# Wireless_Switch.net
KiCad netlist of a schematic drawn in EAGLE
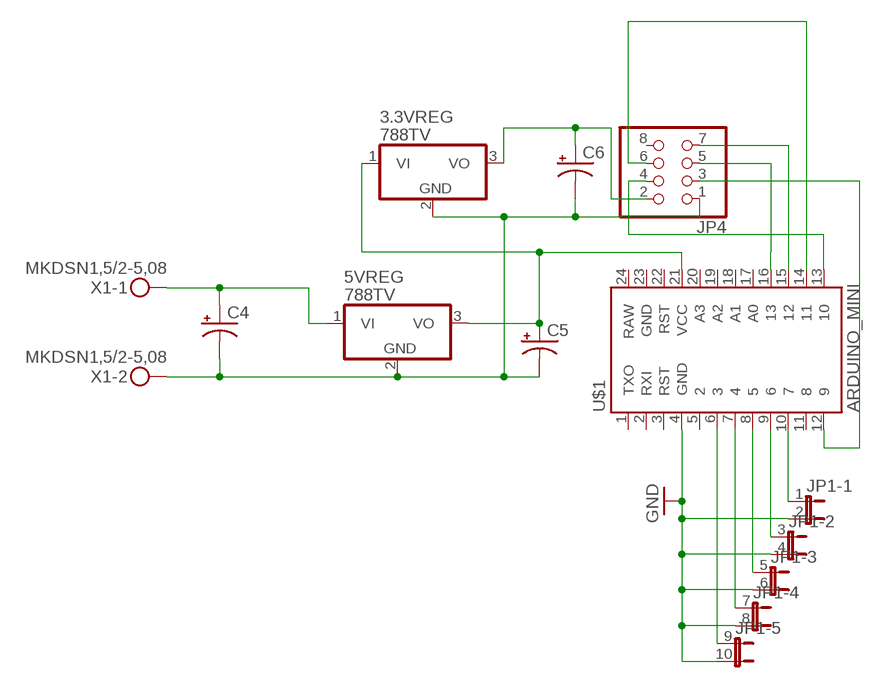
[diagram p0: schematic, sheet 1]

(export (version "E")
  (design (tool "Eeschema 10.0.6"))
  (components
    (comp (ref "3.3VREG")
      (value "788TV")
      (footprint "eagle-import:TO220V")
      (libsource (lib "eagle-import") (part "78TV8"))
    )
    (comp (ref "5VREG")
      (value "788TV")
      (footprint "eagle-import:TO220V")
      (libsource (lib "eagle-import") (part "78TV8"))
    )
    (comp (ref "C4")
      (value "CPOL-USE3.5-8")
      (footprint "eagle-import:E3,5-8")
      (libsource (lib "eagle-import") (part "CPOL-USE3.5-8"))
    )
    (comp (ref "C5")
      (value "CPOL-USE3.5-8")
      (footprint "eagle-import:E3,5-8")
      (libsource (lib "eagle-import") (part "CPOL-USE3.5-8"))
    )
    (comp (ref "C6")
      (value "CPOL-USE2.5-6")
      (footprint "eagle-import:E2,5-6")
      (libsource (lib "eagle-import") (part "CPOL-USE2.5-6"))
    )
    (comp (ref "JP1")
      (value "JP5QE")
      (footprint "eagle-import:JP5Q")
      (libsource (lib "eagle-import") (part "JP5QE"))
    )
    (comp (ref "JP4")
      (value "PINHD-2X4")
      (footprint "eagle-import:2X04")
      (libsource (lib "eagle-import") (part "PINHD-2X4"))
    )
    (comp (ref "U$1")
      (value "ARDUINO_MINI")
      (footprint "eagle-import:ARDUINO_MINI")
      (libsource (lib "eagle-import") (part "ARDUINO_MINI"))
    )
    (comp (ref "X1")
      (value "MKDSN1,5/2-5,08")
      (footprint "eagle-import:MKDSN1,5_2-5,08")
      (libsource (lib "eagle-import") (part "MKDSN1,5/2-5,08"))
    )
  )
  (nets
    (net (code "1") (name "GND") (class "Default")
      (node (ref "JP1") (pin "10") (pinfunction "2_10") (pintype "passive"))
      (node (ref "JP1") (pin "2") (pinfunction "2_2") (pintype "passive"))
      (node (ref "JP1") (pin "4") (pinfunction "2_4") (pintype "passive"))
      (node (ref "JP1") (pin "6") (pinfunction "2_6") (pintype "passive"))
      (node (ref "JP1") (pin "8") (pinfunction "2_8") (pintype "passive"))
      (node (ref "U$1") (pin "4") (pinfunction "GND_4") (pintype "bidirectional"))
    )
    (net (code "2") (name "Net-(3.3VREG-GND)") (class "Default")
      (node (ref "3.3VREG") (pin "2") (pinfunction "GND_2") (pintype "passive"))
      (node (ref "5VREG") (pin "2") (pinfunction "GND_2") (pintype "passive"))
      (node (ref "C4") (pin "-") (pinfunction "-_-") (pintype "passive"))
      (node (ref "C5") (pin "-") (pinfunction "-_-") (pintype "passive"))
      (node (ref "C6") (pin "-") (pinfunction "-_-") (pintype "passive"))
      (node (ref "JP4") (pin "1") (pinfunction "1_1") (pintype "passive"))
      (node (ref "X1") (pin "2") (pinfunction "KL_2") (pintype "passive"))
    )
    (net (code "3") (name "Net-(3.3VREG-VI)") (class "Default")
      (node (ref "3.3VREG") (pin "1") (pinfunction "VI_1") (pintype "input"))
      (node (ref "5VREG") (pin "3") (pinfunction "VO_3") (pintype "passive"))
      (node (ref "C5") (pin "+") (pinfunction "+_+") (pintype "passive"))
      (node (ref "U$1") (pin "21") (pinfunction "VCC_21") (pintype "bidirectional"))
    )
    (net (code "4") (name "Net-(3.3VREG-VO)") (class "Default")
      (node (ref "3.3VREG") (pin "3") (pinfunction "VO_3") (pintype "passive"))
      (node (ref "C6") (pin "+") (pinfunction "+_+") (pintype "passive"))
      (node (ref "JP4") (pin "2") (pinfunction "2_2") (pintype "passive"))
    )
    (net (code "5") (name "Net-(5VREG-VI)") (class "Default")
      (node (ref "5VREG") (pin "1") (pinfunction "VI_1") (pintype "input"))
      (node (ref "C4") (pin "+") (pinfunction "+_+") (pintype "passive"))
      (node (ref "X1") (pin "1") (pinfunction "KL_1") (pintype "passive"))
    )
    (net (code "6") (name "Net-(JP1B-1)") (class "Default")
      (node (ref "JP1") (pin "3") (pinfunction "1_3") (pintype "passive"))
      (node (ref "U$1") (pin "9") (pinfunction "6_9") (pintype "bidirectional"))
    )
    (net (code "7") (name "Net-(JP1C-1)") (class "Default")
      (node (ref "JP1") (pin "5") (pinfunction "1_5") (pintype "passive"))
      (node (ref "U$1") (pin "8") (pinfunction "5_8") (pintype "bidirectional"))
    )
    (net (code "8") (name "Net-(JP1D-1)") (class "Default")
      (node (ref "JP1") (pin "7") (pinfunction "1_7") (pintype "passive"))
      (node (ref "U$1") (pin "7") (pinfunction "4_7") (pintype "bidirectional"))
    )
    (net (code "9") (name "Net-(JP1E-1)") (class "Default")
      (node (ref "JP1") (pin "9") (pinfunction "1_9") (pintype "passive"))
      (node (ref "U$1") (pin "6") (pinfunction "3_6") (pintype "bidirectional"))
    )
    (net (code "10") (name "Net-(U$1-7)") (class "Default")
      (node (ref "JP1") (pin "1") (pinfunction "1_1") (pintype "passive"))
      (node (ref "U$1") (pin "10") (pinfunction "7_10") (pintype "bidirectional"))
    )
    (net (code "11") (name "Net-(U$1-9)") (class "Default")
      (node (ref "JP4") (pin "3") (pinfunction "3_3") (pintype "passive"))
      (node (ref "U$1") (pin "12") (pinfunction "9_12") (pintype "bidirectional"))
    )
    (net (code "12") (name "Net-(U$1-10)") (class "Default")
      (node (ref "JP4") (pin "4") (pinfunction "4_4") (pintype "passive"))
      (node (ref "U$1") (pin "13") (pinfunction "10_13") (pintype "bidirectional"))
    )
    (net (code "13") (name "Net-(U$1-11)") (class "Default")
      (node (ref "JP4") (pin "6") (pinfunction "6_6") (pintype "passive"))
      (node (ref "U$1") (pin "14") (pinfunction "11_14") (pintype "bidirectional"))
    )
    (net (code "14") (name "Net-(U$1-12)") (class "Default")
      (node (ref "JP4") (pin "7") (pinfunction "7_7") (pintype "passive"))
      (node (ref "U$1") (pin "15") (pinfunction "12_15") (pintype "bidirectional"))
    )
    (net (code "15") (name "Net-(U$1-13)") (class "Default")
      (node (ref "JP4") (pin "5") (pinfunction "5_5") (pintype "passive"))
      (node (ref "U$1") (pin "16") (pinfunction "13_16") (pintype "bidirectional"))
    )
    (net (code "16") (name "unconnected-(JP4-Pad8)") (class "Default")
      (node (ref "JP4") (pin "8") (pinfunction "8_8") (pintype "passive"))
    )
    (net (code "17") (name "unconnected-(U$1-2-Pad5)") (class "Default")
      (node (ref "U$1") (pin "5") (pinfunction "2_5") (pintype "bidirectional"))
    )
    (net (code "18") (name "unconnected-(U$1-8-Pad11)") (class "Default")
      (node (ref "U$1") (pin "11") (pinfunction "8_11") (pintype "bidirectional"))
    )
    (net (code "19") (name "unconnected-(U$1-A0-Pad17)") (class "Default")
      (node (ref "U$1") (pin "17") (pinfunction "A0_17") (pintype "bidirectional"))
    )
    (net (code "20") (name "unconnected-(U$1-A1-Pad18)") (class "Default")
      (node (ref "U$1") (pin "18") (pinfunction "A1_18") (pintype "bidirectional"))
    )
    (net (code "21") (name "unconnected-(U$1-A2-Pad19)") (class "Default")
      (node (ref "U$1") (pin "19") (pinfunction "A2_19") (pintype "bidirectional"))
    )
    (net (code "22") (name "unconnected-(U$1-A3-Pad20)") (class "Default")
      (node (ref "U$1") (pin "20") (pinfunction "A3_20") (pintype "bidirectional"))
    )
    (net (code "23") (name "unconnected-(U$1-GND-Pad23)") (class "Default")
      (node (ref "U$1") (pin "23") (pinfunction "GND_23") (pintype "bidirectional"))
    )
    (net (code "24") (name "unconnected-(U$1-RAW-Pad24)") (class "Default")
      (node (ref "U$1") (pin "24") (pinfunction "RAW_24") (pintype "bidirectional"))
    )
    (net (code "25") (name "unconnected-(U$1-RST-Pad3)") (class "Default")
      (node (ref "U$1") (pin "3") (pinfunction "RST_3") (pintype "bidirectional"))
    )
    (net (code "26") (name "unconnected-(U$1-RST-Pad22)") (class "Default")
      (node (ref "U$1") (pin "22") (pinfunction "RST_22") (pintype "bidirectional"))
    )
    (net (code "27") (name "unconnected-(U$1-RXI-Pad2)") (class "Default")
      (node (ref "U$1") (pin "2") (pinfunction "RXI_2") (pintype "bidirectional"))
    )
    (net (code "28") (name "unconnected-(U$1-TXO-Pad1)") (class "Default")
      (node (ref "U$1") (pin "1") (pinfunction "TXO_1") (pintype "bidirectional"))
    )
  )
)
